# 737NG_MCDU_SidePanel_v_01.net
KiCad netlist of a schematic drawn in EasyEDA
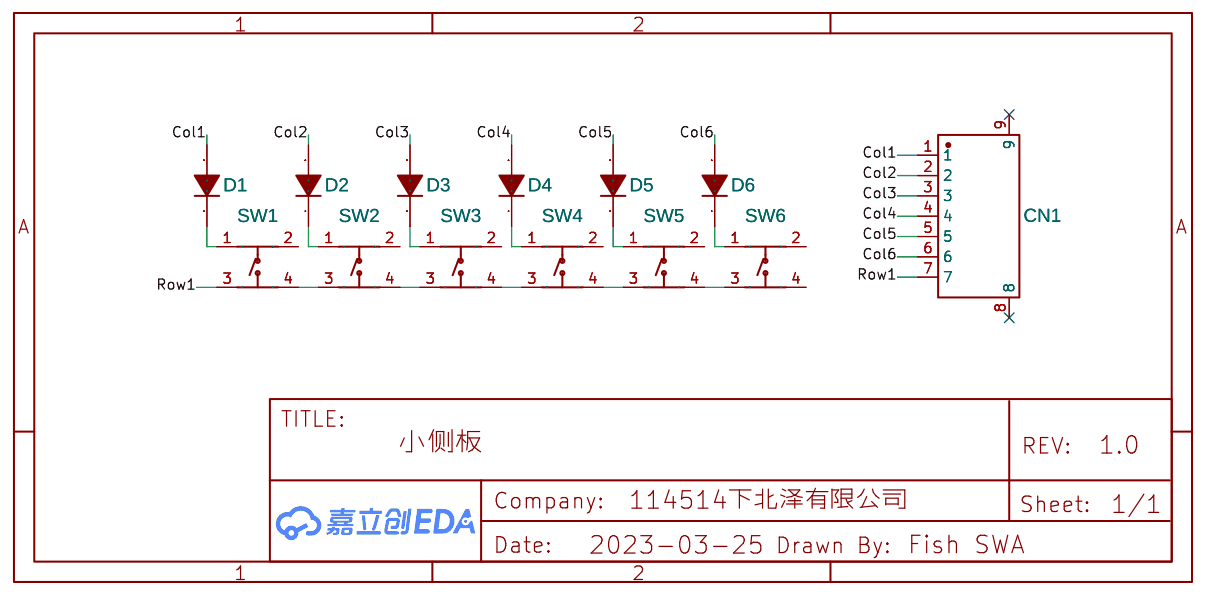
[diagram p0: schematic sheet]

(export (version "E")
  (design (tool "Eeschema 10.0.6"))
  (components
    (comp (ref "CN1")
      (value "A1002WR-S-7P")
      (fields (field (name "BOM_Supplier Part") "C239525"))
      (libsource (lib "") (part "A1002WR-S-7P"))
    )
    (comp (ref "D1")
      (value "1N4148WS T4")
      (fields (field (name "BOM_Manufacturer Part") "1N4148WS") (field (name "BOM_Supplier Part") "C2128"))
      (libsource (lib "") (part "1N4148WS T4"))
    )
    (comp (ref "D2")
      (value "1N4148WS T4")
      (fields (field (name "BOM_Manufacturer Part") "1N4148WS") (field (name "BOM_Supplier Part") "C2128"))
      (libsource (lib "") (part "1N4148WS T4"))
    )
    (comp (ref "D3")
      (value "1N4148WS T4")
      (fields (field (name "BOM_Manufacturer Part") "1N4148WS") (field (name "BOM_Supplier Part") "C2128"))
      (libsource (lib "") (part "1N4148WS T4"))
    )
    (comp (ref "D4")
      (value "1N4148WS T4")
      (fields (field (name "BOM_Manufacturer Part") "1N4148WS") (field (name "BOM_Supplier Part") "C2128"))
      (libsource (lib "") (part "1N4148WS T4"))
    )
    (comp (ref "D5")
      (value "1N4148WS T4")
      (fields (field (name "BOM_Manufacturer Part") "1N4148WS") (field (name "BOM_Supplier Part") "C2128"))
      (libsource (lib "") (part "1N4148WS T4"))
    )
    (comp (ref "D6")
      (value "1N4148WS T4")
      (fields (field (name "BOM_Manufacturer Part") "1N4148WS") (field (name "BOM_Supplier Part") "C2128"))
      (libsource (lib "") (part "1N4148WS T4"))
    )
    (comp (ref "SW1")
      (value "PTS525SM15SMTR2LFS")
      (fields (field (name "BOM_Supplier Part") "C221856"))
      (libsource (lib "") (part "PTS525SM15SMTR2LFS"))
    )
    (comp (ref "SW2")
      (value "PTS525SM15SMTR2LFS")
      (fields (field (name "BOM_Supplier Part") "C221856"))
      (libsource (lib "") (part "PTS525SM15SMTR2LFS"))
    )
    (comp (ref "SW3")
      (value "PTS525SM15SMTR2LFS")
      (fields (field (name "BOM_Supplier Part") "C221856"))
      (libsource (lib "") (part "PTS525SM15SMTR2LFS"))
    )
    (comp (ref "SW4")
      (value "PTS525SM15SMTR2LFS")
      (fields (field (name "BOM_Supplier Part") "C221856"))
      (libsource (lib "") (part "PTS525SM15SMTR2LFS"))
    )
    (comp (ref "SW5")
      (value "PTS525SM15SMTR2LFS")
      (fields (field (name "BOM_Supplier Part") "C221856"))
      (libsource (lib "") (part "PTS525SM15SMTR2LFS"))
    )
    (comp (ref "SW6")
      (value "PTS525SM15SMTR2LFS")
      (fields (field (name "BOM_Supplier Part") "C221856"))
      (libsource (lib "") (part "PTS525SM15SMTR2LFS"))
    )
  )
  (nets
    (net (code "1") (name "/Col1") (class "Default")
      (node (ref "CN1") (pin "1") (pinfunction "1_1") (pintype "unspecified"))
      (node (ref "D1") (pin "2") (pinfunction "A_2") (pintype "unspecified"))
    )
    (net (code "2") (name "/Col2") (class "Default")
      (node (ref "CN1") (pin "2") (pinfunction "2_2") (pintype "unspecified"))
      (node (ref "D2") (pin "2") (pinfunction "A_2") (pintype "unspecified"))
    )
    (net (code "3") (name "/Col3") (class "Default")
      (node (ref "CN1") (pin "3") (pinfunction "3_3") (pintype "unspecified"))
      (node (ref "D3") (pin "2") (pinfunction "A_2") (pintype "unspecified"))
    )
    (net (code "4") (name "/Col4") (class "Default")
      (node (ref "CN1") (pin "4") (pinfunction "4_4") (pintype "unspecified"))
      (node (ref "D4") (pin "2") (pinfunction "A_2") (pintype "unspecified"))
    )
    (net (code "5") (name "/Col5") (class "Default")
      (node (ref "CN1") (pin "5") (pinfunction "5_5") (pintype "unspecified"))
      (node (ref "D5") (pin "2") (pinfunction "A_2") (pintype "unspecified"))
    )
    (net (code "6") (name "/Col6") (class "Default")
      (node (ref "CN1") (pin "6") (pinfunction "6_6") (pintype "unspecified"))
      (node (ref "D6") (pin "2") (pinfunction "A_2") (pintype "unspecified"))
    )
    (net (code "7") (name "/Row1") (class "Default")
      (node (ref "CN1") (pin "7") (pinfunction "7_7") (pintype "unspecified"))
      (node (ref "SW1") (pin "3") (pinfunction "3_3") (pintype "unspecified"))
    )
    (net (code "8") (name "Net-(D1-K)") (class "Default")
      (node (ref "D1") (pin "1") (pinfunction "K_1") (pintype "unspecified"))
      (node (ref "SW1") (pin "1") (pinfunction "1_1") (pintype "unspecified"))
    )
    (net (code "9") (name "Net-(D2-K)") (class "Default")
      (node (ref "D2") (pin "1") (pinfunction "K_1") (pintype "unspecified"))
      (node (ref "SW2") (pin "1") (pinfunction "1_1") (pintype "unspecified"))
    )
    (net (code "10") (name "Net-(D3-K)") (class "Default")
      (node (ref "D3") (pin "1") (pinfunction "K_1") (pintype "unspecified"))
      (node (ref "SW3") (pin "1") (pinfunction "1_1") (pintype "unspecified"))
    )
    (net (code "11") (name "Net-(D4-K)") (class "Default")
      (node (ref "D4") (pin "1") (pinfunction "K_1") (pintype "unspecified"))
      (node (ref "SW4") (pin "1") (pinfunction "1_1") (pintype "unspecified"))
    )
    (net (code "12") (name "Net-(D5-K)") (class "Default")
      (node (ref "D5") (pin "1") (pinfunction "K_1") (pintype "unspecified"))
      (node (ref "SW5") (pin "1") (pinfunction "1_1") (pintype "unspecified"))
    )
    (net (code "13") (name "Net-(D6-K)") (class "Default")
      (node (ref "D6") (pin "1") (pinfunction "K_1") (pintype "unspecified"))
      (node (ref "SW6") (pin "1") (pinfunction "1_1") (pintype "unspecified"))
    )
    (net (code "14") (name "Net-(SW1-Pad4)") (class "Default")
      (node (ref "SW1") (pin "4") (pinfunction "4_4") (pintype "unspecified"))
      (node (ref "SW2") (pin "3") (pinfunction "3_3") (pintype "unspecified"))
    )
    (net (code "15") (name "Net-(SW2-Pad4)") (class "Default")
      (node (ref "SW2") (pin "4") (pinfunction "4_4") (pintype "unspecified"))
      (node (ref "SW3") (pin "3") (pinfunction "3_3") (pintype "unspecified"))
    )
    (net (code "16") (name "Net-(SW3-Pad4)") (class "Default")
      (node (ref "SW3") (pin "4") (pinfunction "4_4") (pintype "unspecified"))
      (node (ref "SW4") (pin "3") (pinfunction "3_3") (pintype "unspecified"))
    )
    (net (code "17") (name "Net-(SW4-Pad4)") (class "Default")
      (node (ref "SW4") (pin "4") (pinfunction "4_4") (pintype "unspecified"))
      (node (ref "SW5") (pin "3") (pinfunction "3_3") (pintype "unspecified"))
    )
    (net (code "18") (name "Net-(SW5-Pad4)") (class "Default")
      (node (ref "SW5") (pin "4") (pinfunction "4_4") (pintype "unspecified"))
      (node (ref "SW6") (pin "3") (pinfunction "3_3") (pintype "unspecified"))
    )
    (net (code "19") (name "unconnected-(CN1-Pad8)") (class "Default")
      (node (ref "CN1") (pin "8") (pinfunction "8_8") (pintype "unspecified+no_connect"))
    )
    (net (code "20") (name "unconnected-(CN1-Pad9)") (class "Default")
      (node (ref "CN1") (pin "9") (pinfunction "9_9") (pintype "unspecified+no_connect"))
    )
    (net (code "21") (name "unconnected-(SW1-Pad2)") (class "Default")
      (node (ref "SW1") (pin "2") (pinfunction "2_2") (pintype "unspecified"))
    )
    (net (code "22") (name "unconnected-(SW2-Pad2)") (class "Default")
      (node (ref "SW2") (pin "2") (pinfunction "2_2") (pintype "unspecified"))
    )
    (net (code "23") (name "unconnected-(SW3-Pad2)") (class "Default")
      (node (ref "SW3") (pin "2") (pinfunction "2_2") (pintype "unspecified"))
    )
    (net (code "24") (name "unconnected-(SW4-Pad2)") (class "Default")
      (node (ref "SW4") (pin "2") (pinfunction "2_2") (pintype "unspecified"))
    )
    (net (code "25") (name "unconnected-(SW5-Pad2)") (class "Default")
      (node (ref "SW5") (pin "2") (pinfunction "2_2") (pintype "unspecified"))
    )
    (net (code "26") (name "unconnected-(SW6-Pad2)") (class "Default")
      (node (ref "SW6") (pin "2") (pinfunction "2_2") (pintype "unspecified"))
    )
    (net (code "27") (name "unconnected-(SW6-Pad4)") (class "Default")
      (node (ref "SW6") (pin "4") (pinfunction "4_4") (pintype "unspecified"))
    )
  )
)
